# record_revc_ina225.net
KiCad netlist of a schematic drawn in EAGLE
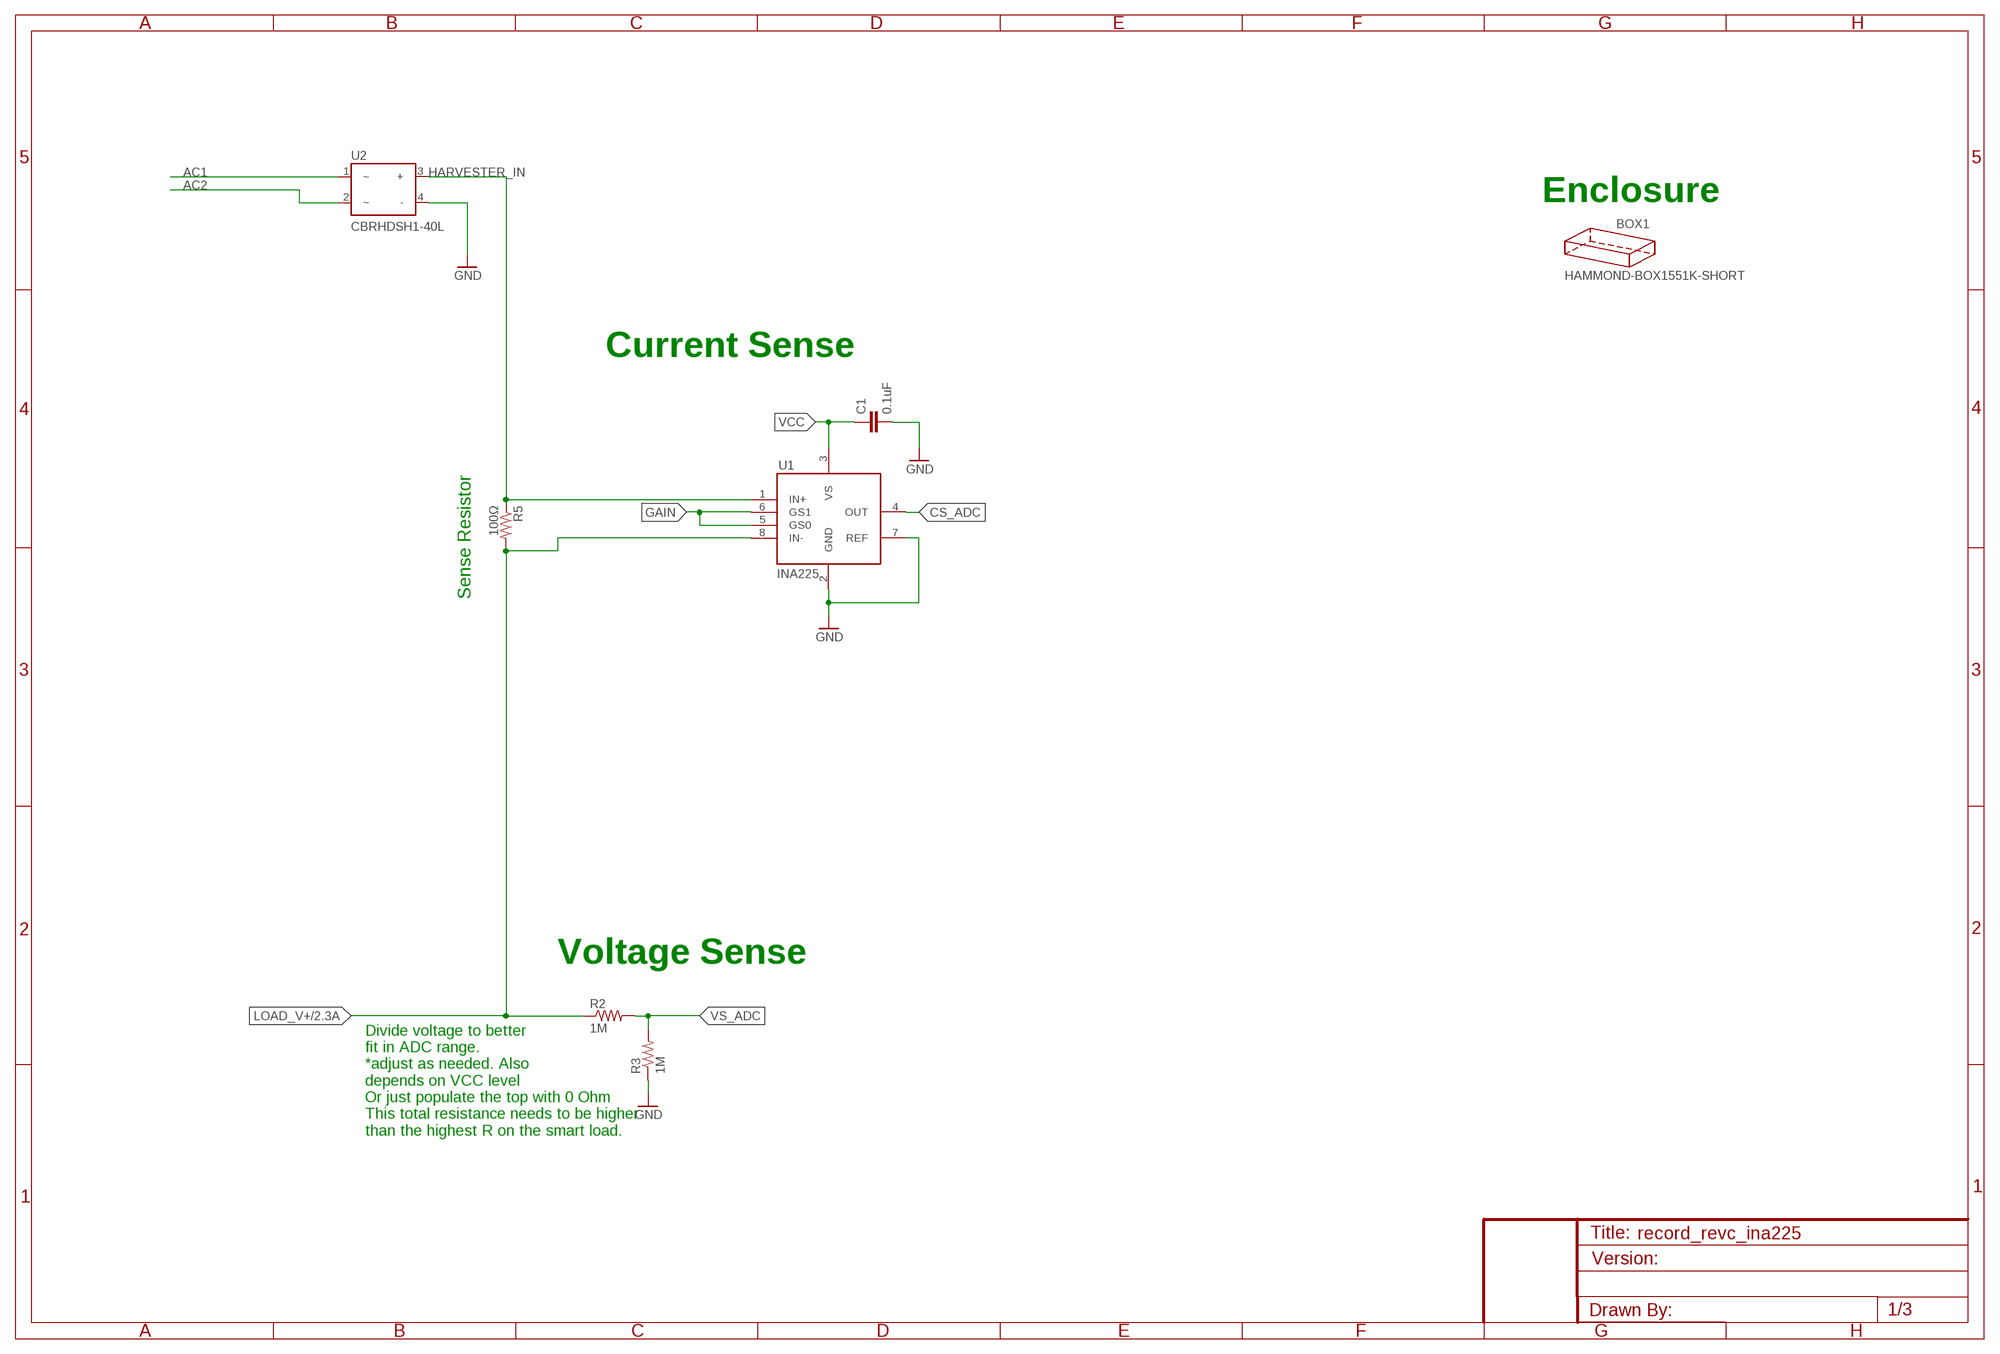
[diagram p0: schematic, sheet 1]
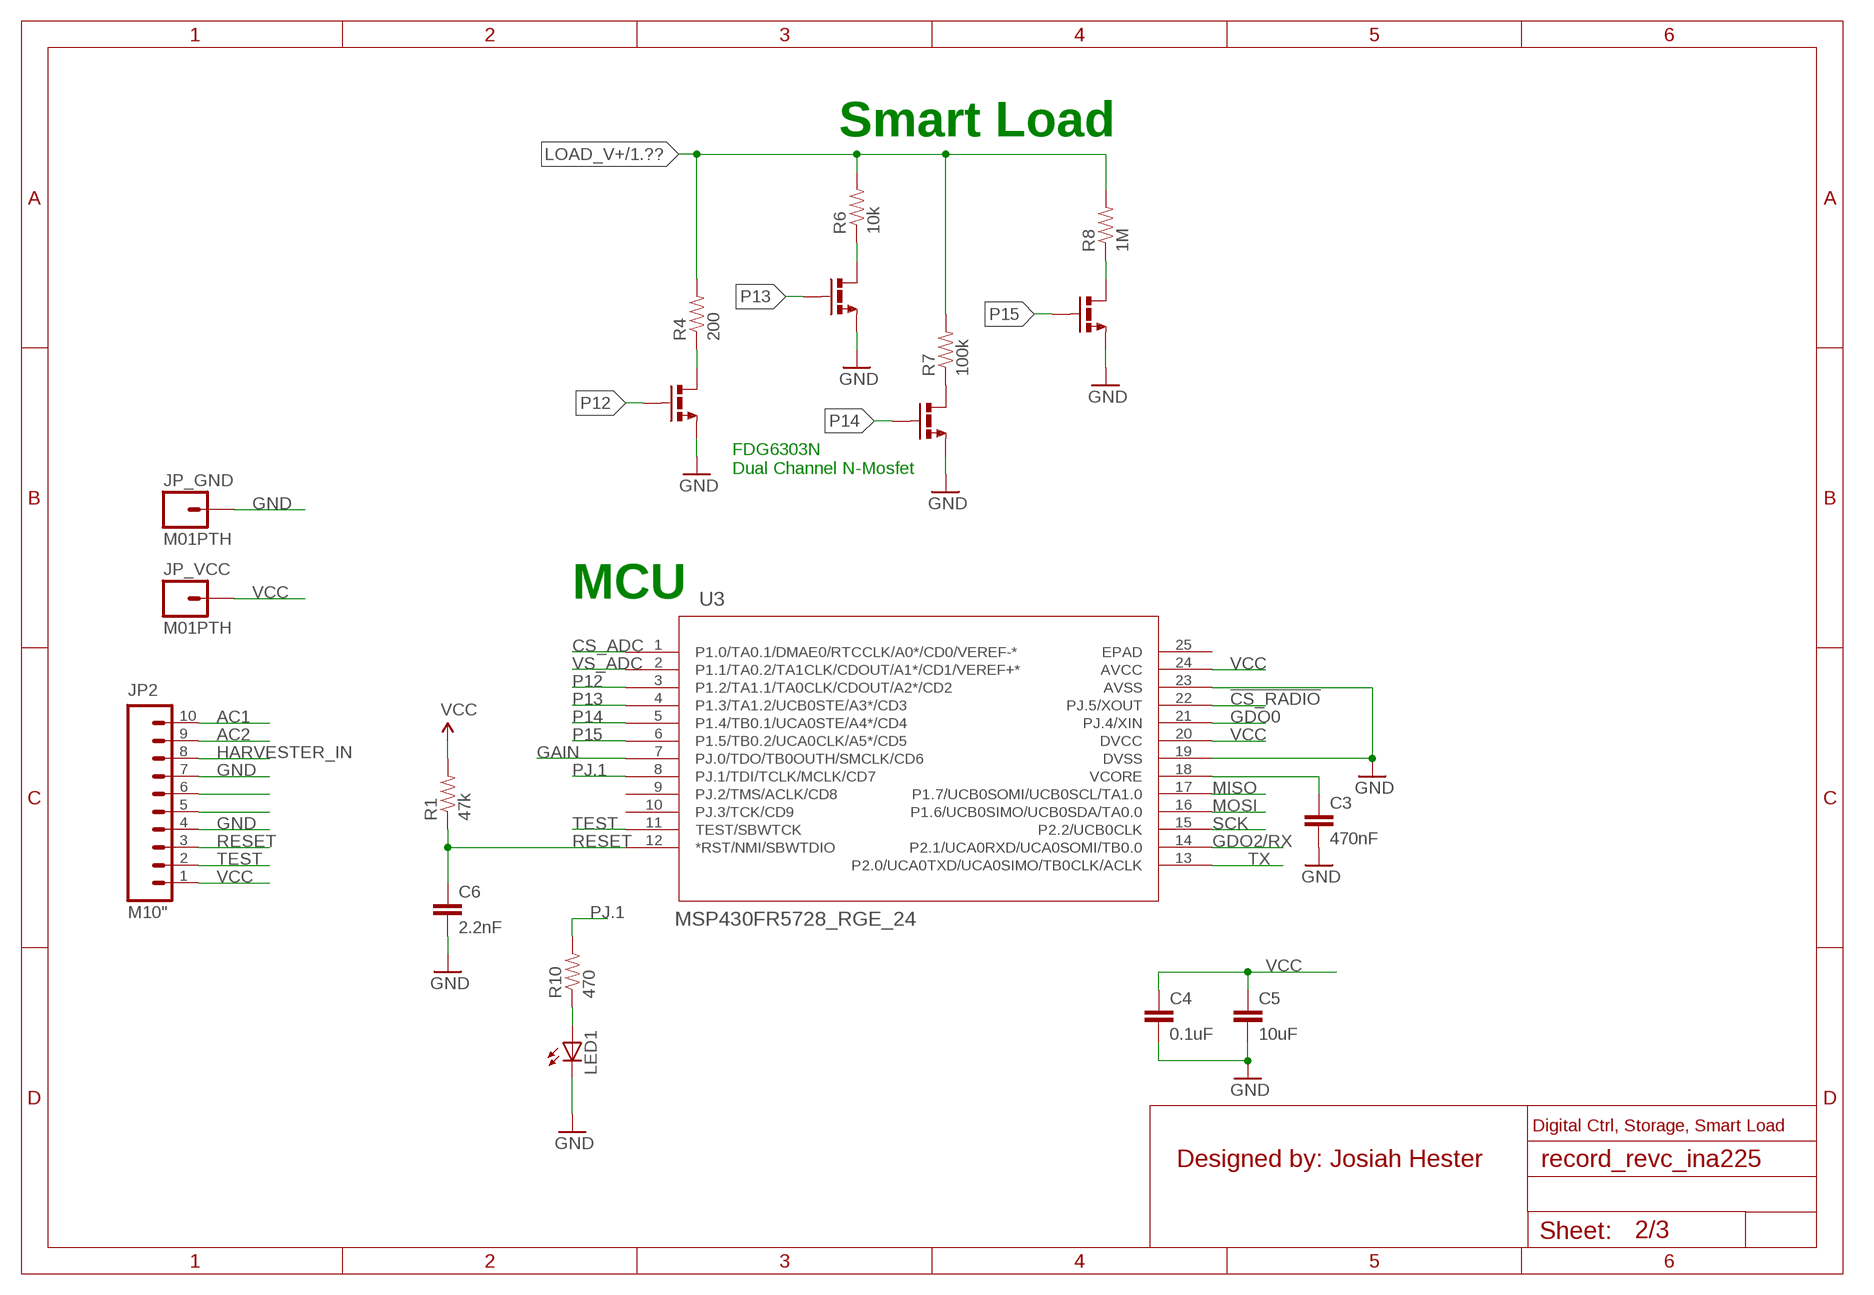
[diagram p1: schematic, sheet 2]
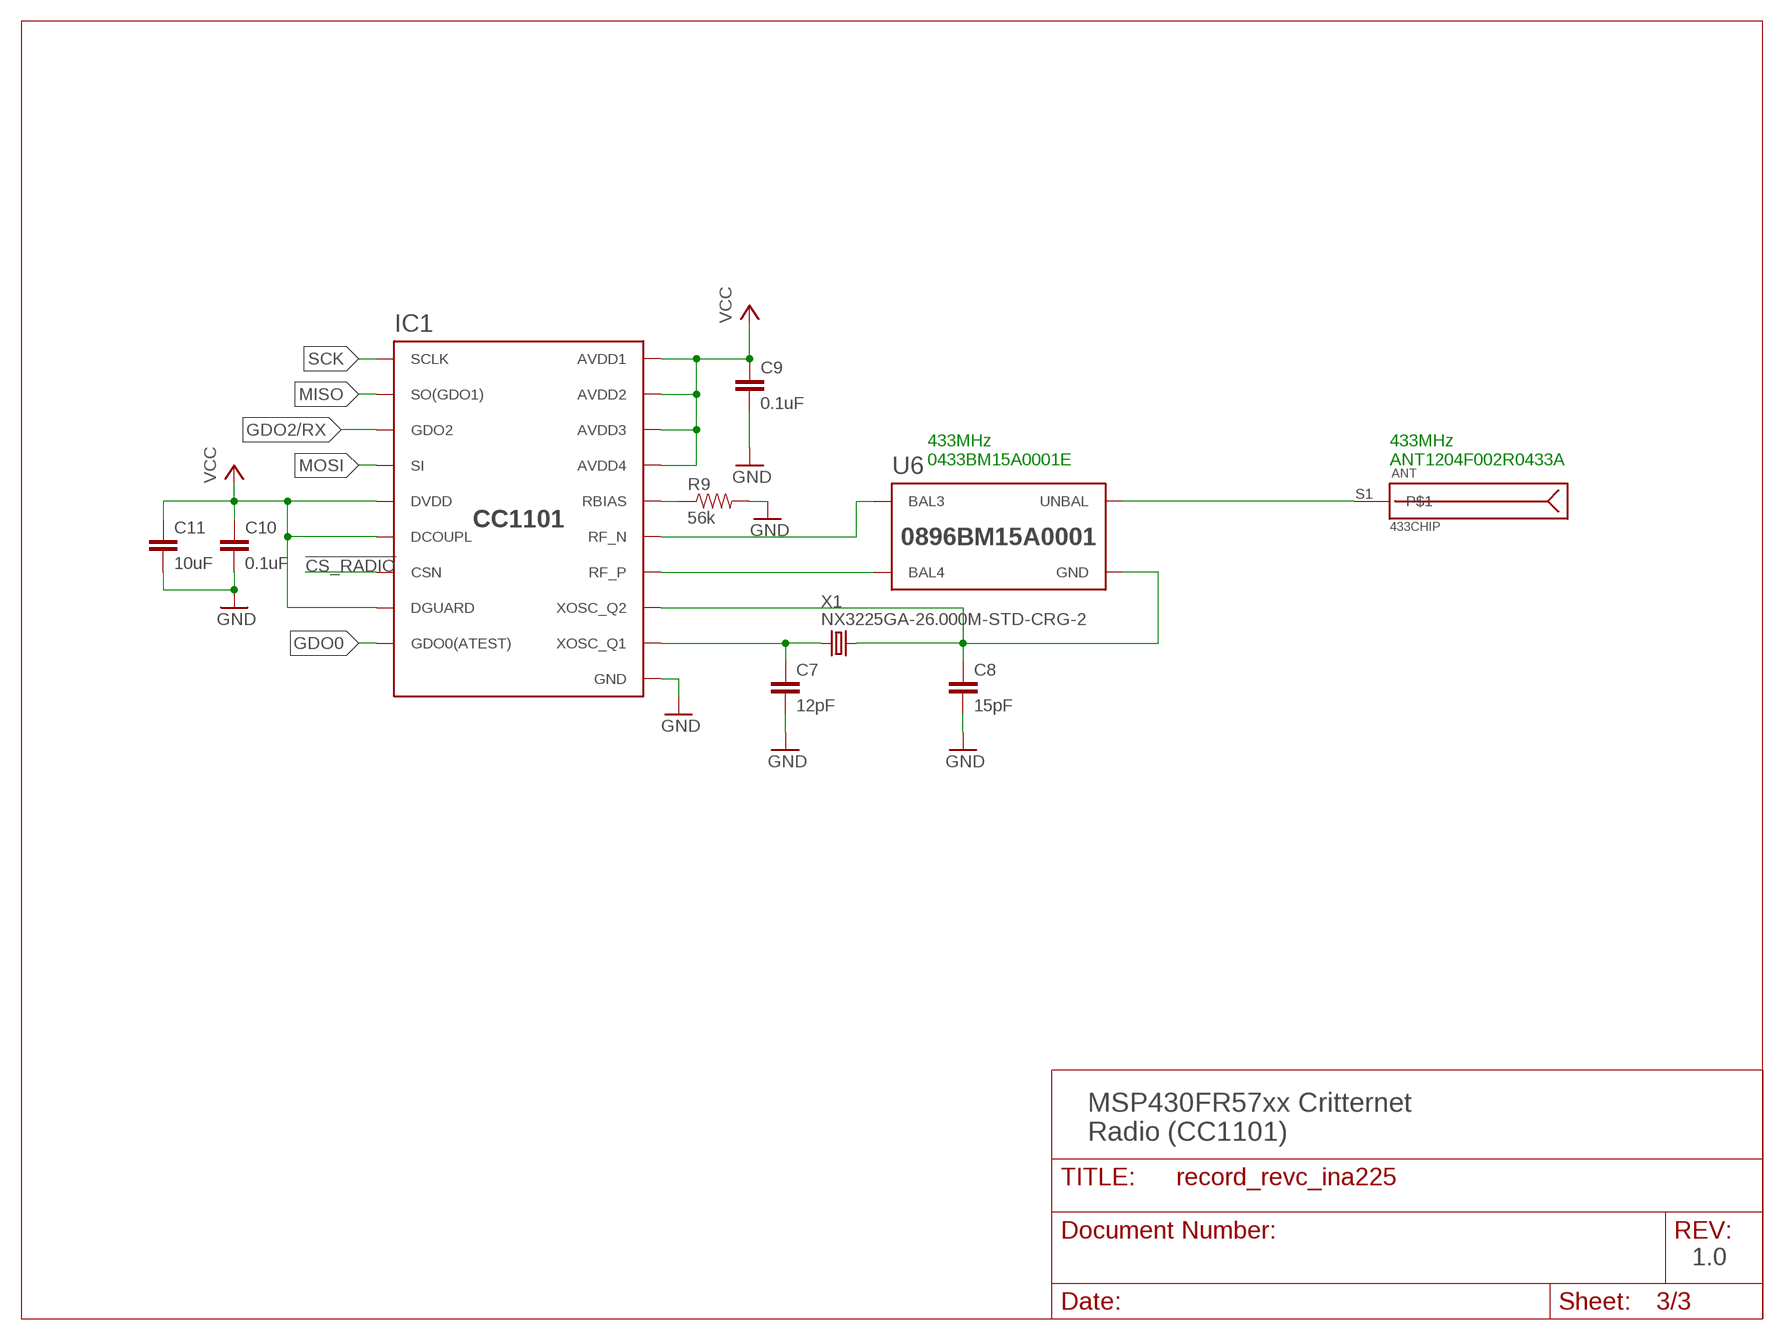
[diagram p2: schematic, sheet 3]

(export (version "E")
  (design (tool "Eeschema 10.0.6"))
  (components
    (comp (ref "C3")
      (value "470nF")
      (footprint "eagle-import:0805")
      (libsource (lib "eagle-import") (part "1UF-25V-10%(0805)"))
    )
    (comp (ref "C4")
      (value "0.1uF")
      (footprint "eagle-import:0805")
      (libsource (lib "eagle-import") (part "1UF-25V-10%(0805)"))
    )
    (comp (ref "C5")
      (value "10uF")
      (footprint "eagle-import:0805")
      (libsource (lib "eagle-import") (part "1UF-25V-10%(0805)"))
    )
    (comp (ref "C6")
      (value "2.2nF")
      (footprint "eagle-import:0805")
      (libsource (lib "eagle-import") (part "1UF-25V-10%(0805)"))
    )
    (comp (ref "JP2")
      (value "M10\"")
      (footprint "eagle-import:1X10")
      (libsource (lib "eagle-import") (part "M10{dblquote}"))
    )
    (comp (ref "JP_GND")
      (value "M01PTH")
      (footprint "eagle-import:1X01")
      (libsource (lib "eagle-import") (part "M01PTH"))
    )
    (comp (ref "JP_VCC")
      (value "M01PTH")
      (footprint "eagle-import:1X01")
      (libsource (lib "eagle-import") (part "M01PTH"))
    )
    (comp (ref "LED1")
      (value "LED0603")
      (footprint "eagle-import:LED-0603")
      (libsource (lib "eagle-import") (part "LED0603"))
    )
    (comp (ref "R1")
      (value "47k")
      (footprint "eagle-import:0805")
      (libsource (lib "eagle-import") (part "0.22OHM1/4W1%(0805)"))
    )
    (comp (ref "R4")
      (value "200")
      (footprint "eagle-import:0805")
      (libsource (lib "eagle-import") (part "0.22OHM1/4W1%(0805)"))
    )
    (comp (ref "R6")
      (value "10k")
      (footprint "eagle-import:0805")
      (libsource (lib "eagle-import") (part "0.22OHM1/4W1%(0805)"))
    )
    (comp (ref "R7")
      (value "100k")
      (footprint "eagle-import:0805")
      (libsource (lib "eagle-import") (part "0.22OHM1/4W1%(0805)"))
    )
    (comp (ref "R8")
      (value "1M")
      (footprint "eagle-import:0805")
      (libsource (lib "eagle-import") (part "0.22OHM1/4W1%(0805)"))
    )
    (comp (ref "R10")
      (value "470")
      (footprint "eagle-import:0805")
      (libsource (lib "eagle-import") (part "0.22OHM1/4W1%(0805)"))
    )
    (comp (ref "U3")
      (value "MSP430FR5728_RGE_24")
      (footprint "eagle-import:RGE24_2P1X2P1")
      (fields
        (field (name "GENERIC_PART_NUMBER") "MSP430FR5728")
        (field (name "MANUFACTURER") "Texas Instruments")
        (field (name "MANUFACTURER_PART_NUMBER") "msp430fr5728_rge_24")
      )
      (libsource (lib "eagle-import") (part "MSP430FR5728_RGE_24"))
    )
    (comp (ref "U4")
      (value "FDG6303N")
      (footprint "eagle-import:SC70-6")
      (libsource (lib "eagle-import") (part "FDG6303N"))
    )
    (comp (ref "U5")
      (value "FDG6303N")
      (footprint "eagle-import:SC70-6")
      (libsource (lib "eagle-import") (part "FDG6303N"))
    )
    (comp (ref "BOX1")
      (value "HAMMOND-BOX1551K-SHORT")
      (footprint "eagle-import:1551K-SHORT")
      (libsource (lib "eagle-import") (part "HAMMOND-BOX1551K-SHORT"))
    )
    (comp (ref "C1")
      (value "0.1uF")
      (footprint "eagle-import:C0805")
      (libsource (lib "eagle-import") (part "CAP0805"))
    )
    (comp (ref "R2")
      (value "1M")
      (footprint "eagle-import:0805")
      (libsource (lib "eagle-import") (part "SparkFun-Resistors_RESISTOR0805-RES"))
    )
    (comp (ref "R3")
      (value "1M")
      (footprint "eagle-import:0805")
      (libsource (lib "eagle-import") (part "SparkFun-Resistors_RESISTOR0805-RES"))
    )
    (comp (ref "R5")
      (value "100Ω")
      (footprint "eagle-import:0805")
      (libsource (lib "eagle-import") (part "RESISTOR0805-RES"))
    )
    (comp (ref "U1")
      (value "INA225")
      (footprint "eagle-import:MSOP8")
      (libsource (lib "eagle-import") (part "INA225"))
    )
    (comp (ref "U2")
      (value "CBRHDSH1-40L")
      (footprint "eagle-import:HD_DIP4")
      (libsource (lib "eagle-import") (part "CBRHDSH1-40L"))
    )
    (comp (ref "ANT")
      (value "433CHIP")
      (footprint "eagle-import:ANT-433-USP")
      (libsource (lib "eagle-import") (part "433CHIP"))
    )
    (comp (ref "C7")
      (value "12pF")
      (footprint "eagle-import:0603-CAP")
      (libsource (lib "eagle-import") (part "0.1UF-25V(+80/-20%)(0603)"))
    )
    (comp (ref "C8")
      (value "15pF")
      (footprint "eagle-import:0603-CAP")
      (libsource (lib "eagle-import") (part "0.1UF-25V(+80/-20%)(0603)"))
    )
    (comp (ref "C9")
      (value "0.1uF")
      (footprint "eagle-import:0603-CAP")
      (libsource (lib "eagle-import") (part "CAP0603-CAP"))
    )
    (comp (ref "C10")
      (value "0.1uF")
      (footprint "eagle-import:C0805")
      (libsource (lib "eagle-import") (part "CAP0805"))
    )
    (comp (ref "C11")
      (value "10uF")
      (footprint "eagle-import:0805")
      (libsource (lib "eagle-import") (part "1.0UF-25V-+80/-20(0805)"))
    )
    (comp (ref "IC1")
      (value "CC1101")
      (footprint "eagle-import:QLP20")
      (libsource (lib "eagle-import") (part "CC1101"))
    )
    (comp (ref "R9")
      (value "56k")
      (footprint "eagle-import:0603")
      (libsource (lib "eagle-import") (part "0OHM1/10W5%(0603)"))
    )
    (comp (ref "U6")
      (value "0896BM15A0001")
      (footprint "eagle-import:0896BM15A0001")
      (libsource (lib "eagle-import") (part "0896BM15A0001"))
    )
    (comp (ref "X1")
      (value "NX3225GA-26.000M-STD-CRG-2")
      (footprint "eagle-import:XTAL-3.2X2.5")
      (libsource (lib "eagle-import") (part "XTAL-3.2X2.5"))
    )
  )
  (nets
    (net (code "1") (name "AC1") (class "Default")
      (node (ref "JP2") (pin "10") (pinfunction "10_10") (pintype "passive"))
      (node (ref "U2") (pin "1") (pinfunction "~_1") (pintype "bidirectional"))
    )
    (net (code "2") (name "AC2") (class "Default")
      (node (ref "JP2") (pin "9") (pinfunction "9_9") (pintype "passive"))
      (node (ref "U2") (pin "2") (pinfunction "~_2") (pintype "bidirectional"))
    )
    (net (code "3") (name "CS_ADC") (class "Default")
      (node (ref "U1") (pin "4") (pinfunction "OUT_4") (pintype "bidirectional"))
      (node (ref "U3") (pin "1") (pinfunction "P1.0/TA0.1/DMAE0/RTCCLK/A0*/CD0/VEREF-*_1") (pintype "bidirectional"))
    )
    (net (code "4") (name "GAIN") (class "Default")
      (node (ref "U1") (pin "5") (pinfunction "GS0_5") (pintype "bidirectional"))
      (node (ref "U1") (pin "6") (pinfunction "GS1_6") (pintype "bidirectional"))
      (node (ref "U3") (pin "7") (pinfunction "PJ.0/TDO/TB0OUTH/SMCLK/CD6_7") (pintype "bidirectional"))
    )
    (net (code "5") (name "GDO0") (class "Default")
      (node (ref "IC1") (pin "6") (pinfunction "GDO0(ATEST)_6") (pintype "bidirectional"))
      (node (ref "U3") (pin "21") (pinfunction "PJ.4/XIN_21") (pintype "bidirectional"))
    )
    (net (code "6") (name "GDO2{slash}RX") (class "Default")
      (node (ref "IC1") (pin "3") (pinfunction "GDO2_3") (pintype "bidirectional"))
      (node (ref "JP2") (pin "6") (pinfunction "6_6") (pintype "passive"))
      (node (ref "U3") (pin "14") (pinfunction "P2.1/UCA0RXD/UCA0SOMI/TB0.0_14") (pintype "bidirectional"))
    )
    (net (code "7") (name "GND") (class "Default")
      (node (ref "C1") (pin "2") (pinfunction "2_2") (pintype "passive"))
      (node (ref "C10") (pin "2") (pinfunction "2_2") (pintype "passive"))
      (node (ref "C11") (pin "2") (pinfunction "2_2") (pintype "passive"))
      (node (ref "C3") (pin "2") (pinfunction "2_2") (pintype "passive"))
      (node (ref "C4") (pin "2") (pinfunction "2_2") (pintype "passive"))
      (node (ref "C5") (pin "2") (pinfunction "2_2") (pintype "passive"))
      (node (ref "C6") (pin "2") (pinfunction "2_2") (pintype "passive"))
      (node (ref "C7") (pin "2") (pinfunction "2_2") (pintype "passive"))
      (node (ref "C8") (pin "2") (pinfunction "2_2") (pintype "passive"))
      (node (ref "C9") (pin "2") (pinfunction "2_2") (pintype "passive"))
      (node (ref "IC1") (pin "16") (pinfunction "GND_16") (pintype "bidirectional"))
      (node (ref "IC1") (pin "19") (pinfunction "GND_19") (pintype "bidirectional"))
      (node (ref "IC1") (pin "GND") (pinfunction "GND_GND") (pintype "bidirectional"))
      (node (ref "IC1") (pin "GND1") (pinfunction "GND_GND1") (pintype "bidirectional"))
      (node (ref "IC1") (pin "GND2") (pinfunction "GND_GND2") (pintype "bidirectional"))
      (node (ref "IC1") (pin "GND3") (pinfunction "GND_GND3") (pintype "bidirectional"))
      (node (ref "IC1") (pin "GND4") (pinfunction "GND_GND4") (pintype "bidirectional"))
      (node (ref "IC1") (pin "GND5") (pinfunction "GND_GND5") (pintype "bidirectional"))
      (node (ref "JP2") (pin "4") (pinfunction "4_4") (pintype "passive"))
      (node (ref "JP2") (pin "7") (pinfunction "7_7") (pintype "passive"))
      (node (ref "JP_GND") (pin "1") (pinfunction "1_1") (pintype "passive"))
      (node (ref "LED1") (pin "C") (pinfunction "C_C") (pintype "passive"))
      (node (ref "R3") (pin "1") (pinfunction "1_1") (pintype "passive"))
      (node (ref "R9") (pin "2") (pinfunction "2_2") (pintype "passive"))
      (node (ref "U1") (pin "2") (pinfunction "GND_2") (pintype "bidirectional"))
      (node (ref "U1") (pin "7") (pinfunction "REF_7") (pintype "bidirectional"))
      (node (ref "U2") (pin "4") (pinfunction "-_4") (pintype "bidirectional"))
      (node (ref "U3") (pin "19") (pinfunction "DVSS_19") (pintype "power_in"))
      (node (ref "U3") (pin "23") (pinfunction "AVSS_23") (pintype "power_in"))
      (node (ref "U4") (pin "1") (pinfunction "S2_1") (pintype "passive"))
      (node (ref "U4") (pin "4") (pinfunction "S1_4") (pintype "passive"))
      (node (ref "U5") (pin "1") (pinfunction "S2_1") (pintype "passive"))
      (node (ref "U5") (pin "4") (pinfunction "S1_4") (pintype "passive"))
    )
    (net (code "8") (name "HARVESTER_IN") (class "Default")
      (node (ref "JP2") (pin "8") (pinfunction "8_8") (pintype "passive"))
      (node (ref "R5") (pin "1") (pinfunction "1_1") (pintype "passive"))
      (node (ref "U1") (pin "1") (pinfunction "IN+_1") (pintype "bidirectional"))
      (node (ref "U2") (pin "3") (pinfunction "+_3") (pintype "bidirectional"))
    )
    (net (code "9") (name "LOAD_V+") (class "Default")
      (node (ref "R2") (pin "1") (pinfunction "1_1") (pintype "passive"))
      (node (ref "R4") (pin "2") (pinfunction "2_2") (pintype "passive"))
      (node (ref "R5") (pin "2") (pinfunction "2_2") (pintype "passive"))
      (node (ref "R6") (pin "2") (pinfunction "2_2") (pintype "passive"))
      (node (ref "R7") (pin "2") (pinfunction "2_2") (pintype "passive"))
      (node (ref "R8") (pin "2") (pinfunction "2_2") (pintype "passive"))
      (node (ref "U1") (pin "8") (pinfunction "IN-_8") (pintype "bidirectional"))
    )
    (net (code "10") (name "MISO") (class "Default")
      (node (ref "IC1") (pin "2") (pinfunction "SO(GDO1)_2") (pintype "bidirectional"))
      (node (ref "U3") (pin "17") (pinfunction "P1.7/UCB0SOMI/UCB0SCL/TA1.0_17") (pintype "bidirectional"))
    )
    (net (code "11") (name "MOSI") (class "Default")
      (node (ref "IC1") (pin "20") (pinfunction "SI_20") (pintype "bidirectional"))
      (node (ref "U3") (pin "16") (pinfunction "P1.6/UCB0SIMO/UCB0SDA/TA0.0_16") (pintype "bidirectional"))
    )
    (net (code "12") (name "Net-(ANT-P$1)") (class "Default")
      (node (ref "ANT") (pin "S1") (pinfunction "P$1_S1") (pintype "bidirectional"))
      (node (ref "U6") (pin "1") (pinfunction "UNBAL_1") (pintype "bidirectional"))
    )
    (net (code "13") (name "Net-(IC1-RBIAS)") (class "Default")
      (node (ref "IC1") (pin "17") (pinfunction "RBIAS_17") (pintype "bidirectional"))
      (node (ref "R9") (pin "1") (pinfunction "1_1") (pintype "passive"))
    )
    (net (code "14") (name "Net-(IC1-RF_N)") (class "Default")
      (node (ref "IC1") (pin "13") (pinfunction "RF_N_13") (pintype "bidirectional"))
      (node (ref "U6") (pin "3") (pinfunction "BAL3_3") (pintype "bidirectional"))
    )
    (net (code "15") (name "Net-(IC1-RF_P)") (class "Default")
      (node (ref "IC1") (pin "12") (pinfunction "RF_P_12") (pintype "bidirectional"))
      (node (ref "U6") (pin "4") (pinfunction "BAL4_4") (pintype "bidirectional"))
    )
    (net (code "16") (name "Net-(IC1-XOSC_Q1)") (class "Default")
      (node (ref "C7") (pin "1") (pinfunction "1_1") (pintype "passive"))
      (node (ref "IC1") (pin "8") (pinfunction "XOSC_Q1_8") (pintype "bidirectional"))
      (node (ref "X1") (pin "1") (pinfunction "1_1") (pintype "passive"))
    )
    (net (code "17") (name "Net-(IC1-XOSC_Q2)") (class "Default")
      (node (ref "C8") (pin "1") (pinfunction "1_1") (pintype "passive"))
      (node (ref "IC1") (pin "10") (pinfunction "XOSC_Q2_10") (pintype "bidirectional"))
      (node (ref "U6") (pin "2") (pinfunction "GND_2") (pintype "bidirectional"))
      (node (ref "U6") (pin "5") (pinfunction "GND_5") (pintype "bidirectional"))
      (node (ref "U6") (pin "6") (pinfunction "GND_6") (pintype "bidirectional"))
      (node (ref "X1") (pin "3") (pinfunction "2_3") (pintype "passive"))
    )
    (net (code "18") (name "Net-(LED1-PadA)") (class "Default")
      (node (ref "LED1") (pin "A") (pinfunction "A_A") (pintype "passive"))
      (node (ref "R10") (pin "1") (pinfunction "1_1") (pintype "passive"))
    )
    (net (code "19") (name "Net-(U3-VCORE)") (class "Default")
      (node (ref "C3") (pin "1") (pinfunction "1_1") (pintype "passive"))
      (node (ref "U3") (pin "18") (pinfunction "VCORE_18") (pintype "power_in"))
    )
    (net (code "20") (name "Net-(U4-D1)") (class "Default")
      (node (ref "R4") (pin "1") (pinfunction "1_1") (pintype "passive"))
      (node (ref "U4") (pin "3") (pinfunction "D1_3") (pintype "passive"))
    )
    (net (code "21") (name "Net-(U4-D2)") (class "Default")
      (node (ref "R6") (pin "1") (pinfunction "1_1") (pintype "passive"))
      (node (ref "U4") (pin "6") (pinfunction "D2_6") (pintype "passive"))
    )
    (net (code "22") (name "Net-(U5-D1)") (class "Default")
      (node (ref "R7") (pin "1") (pinfunction "1_1") (pintype "passive"))
      (node (ref "U5") (pin "3") (pinfunction "D1_3") (pintype "passive"))
    )
    (net (code "23") (name "Net-(U5-D2)") (class "Default")
      (node (ref "R8") (pin "1") (pinfunction "1_1") (pintype "passive"))
      (node (ref "U5") (pin "6") (pinfunction "D2_6") (pintype "passive"))
    )
    (net (code "24") (name "P12") (class "Default")
      (node (ref "U3") (pin "3") (pinfunction "P1.2/TA1.1/TA0CLK/CDOUT/A2*/CD2_3") (pintype "bidirectional"))
      (node (ref "U4") (pin "5") (pinfunction "G1_5") (pintype "passive"))
    )
    (net (code "25") (name "P13") (class "Default")
      (node (ref "U3") (pin "4") (pinfunction "P1.3/TA1.2/UCB0STE/A3*/CD3_4") (pintype "bidirectional"))
      (node (ref "U4") (pin "2") (pinfunction "G2_2") (pintype "passive"))
    )
    (net (code "26") (name "P14") (class "Default")
      (node (ref "U3") (pin "5") (pinfunction "P1.4/TB0.1/UCA0STE/A4*/CD4_5") (pintype "bidirectional"))
      (node (ref "U5") (pin "5") (pinfunction "G1_5") (pintype "passive"))
    )
    (net (code "27") (name "P15") (class "Default")
      (node (ref "U3") (pin "6") (pinfunction "P1.5/TB0.2/UCA0CLK/A5*/CD5_6") (pintype "bidirectional"))
      (node (ref "U5") (pin "2") (pinfunction "G2_2") (pintype "passive"))
    )
    (net (code "28") (name "PJ.1") (class "Default")
      (node (ref "R10") (pin "2") (pinfunction "2_2") (pintype "passive"))
      (node (ref "U3") (pin "8") (pinfunction "PJ.1/TDI/TCLK/MCLK/CD7_8") (pintype "bidirectional"))
    )
    (net (code "29") (name "RESET") (class "Default")
      (node (ref "C6") (pin "1") (pinfunction "1_1") (pintype "passive"))
      (node (ref "JP2") (pin "3") (pinfunction "3_3") (pintype "passive"))
      (node (ref "R1") (pin "1") (pinfunction "1_1") (pintype "passive"))
      (node (ref "U3") (pin "12") (pinfunction "*RST/NMI/SBWTDIO_12") (pintype "bidirectional"))
    )
    (net (code "30") (name "SCK") (class "Default")
      (node (ref "IC1") (pin "1") (pinfunction "SCLK_1") (pintype "bidirectional"))
      (node (ref "U3") (pin "15") (pinfunction "P2.2/UCB0CLK_15") (pintype "bidirectional"))
    )
    (net (code "31") (name "TEST") (class "Default")
      (node (ref "JP2") (pin "2") (pinfunction "2_2") (pintype "passive"))
      (node (ref "U3") (pin "11") (pinfunction "TEST/SBWTCK_11") (pintype "bidirectional"))
    )
    (net (code "32") (name "TX") (class "Default")
      (node (ref "JP2") (pin "5") (pinfunction "5_5") (pintype "passive"))
      (node (ref "U3") (pin "13") (pinfunction "P2.0/UCA0TXD/UCA0SIMO/TB0CLK/ACLK_13") (pintype "bidirectional"))
    )
    (net (code "33") (name "VCC") (class "Default")
      (node (ref "C1") (pin "1") (pinfunction "1_1") (pintype "passive"))
      (node (ref "C10") (pin "1") (pinfunction "1_1") (pintype "passive"))
      (node (ref "C11") (pin "1") (pinfunction "1_1") (pintype "passive"))
      (node (ref "C4") (pin "1") (pinfunction "1_1") (pintype "passive"))
      (node (ref "C5") (pin "1") (pinfunction "1_1") (pintype "passive"))
      (node (ref "C9") (pin "1") (pinfunction "1_1") (pintype "passive"))
      (node (ref "IC1") (pin "11") (pinfunction "AVDD2_11") (pintype "bidirectional"))
      (node (ref "IC1") (pin "14") (pinfunction "AVDD3_14") (pintype "bidirectional"))
      (node (ref "IC1") (pin "15") (pinfunction "AVDD4_15") (pintype "bidirectional"))
      (node (ref "IC1") (pin "18") (pinfunction "DGUARD_18") (pintype "bidirectional"))
      (node (ref "IC1") (pin "4") (pinfunction "DVDD_4") (pintype "bidirectional"))
      (node (ref "IC1") (pin "5") (pinfunction "DCOUPL_5") (pintype "bidirectional"))
      (node (ref "IC1") (pin "9") (pinfunction "AVDD1_9") (pintype "bidirectional"))
      (node (ref "JP2") (pin "1") (pinfunction "1_1") (pintype "passive"))
      (node (ref "JP_VCC") (pin "1") (pinfunction "1_1") (pintype "passive"))
      (node (ref "R1") (pin "2") (pinfunction "2_2") (pintype "passive"))
      (node (ref "U1") (pin "3") (pinfunction "VS_3") (pintype "bidirectional"))
      (node (ref "U3") (pin "20") (pinfunction "DVCC_20") (pintype "power_in"))
      (node (ref "U3") (pin "24") (pinfunction "AVCC_24") (pintype "power_in"))
    )
    (net (code "34") (name "VS_ADC") (class "Default")
      (node (ref "R2") (pin "2") (pinfunction "2_2") (pintype "passive"))
      (node (ref "R3") (pin "2") (pinfunction "2_2") (pintype "passive"))
      (node (ref "U3") (pin "2") (pinfunction "P1.1/TA0.2/TA1CLK/CDOUT/A1*/CD1/VEREF+*_2") (pintype "bidirectional"))
    )
    (net (code "35") (name "unconnected-(U3-EPAD-Pad25)") (class "Default")
      (node (ref "U3") (pin "25") (pinfunction "EPAD_25") (pintype "passive"))
    )
    (net (code "36") (name "unconnected-(U3-PJ.2{slash}TMS{slash}ACLK{slash}CD8-Pad9)") (class "Default")
      (node (ref "U3") (pin "9") (pinfunction "PJ.2/TMS/ACLK/CD8_9") (pintype "bidirectional"))
    )
    (net (code "37") (name "unconnected-(U3-PJ.3{slash}TCK{slash}CD9-Pad10)") (class "Default")
      (node (ref "U3") (pin "10") (pinfunction "PJ.3/TCK/CD9_10") (pintype "bidirectional"))
    )
    (net (code "38") (name "~{CS_RADIO}") (class "Default")
      (node (ref "IC1") (pin "7") (pinfunction "CSN_7") (pintype "bidirectional"))
      (node (ref "U3") (pin "22") (pinfunction "PJ.5/XOUT_22") (pintype "bidirectional"))
    )
  )
)
